# gyroscope.net
KiCad netlist of a schematic drawn in Altium Designer
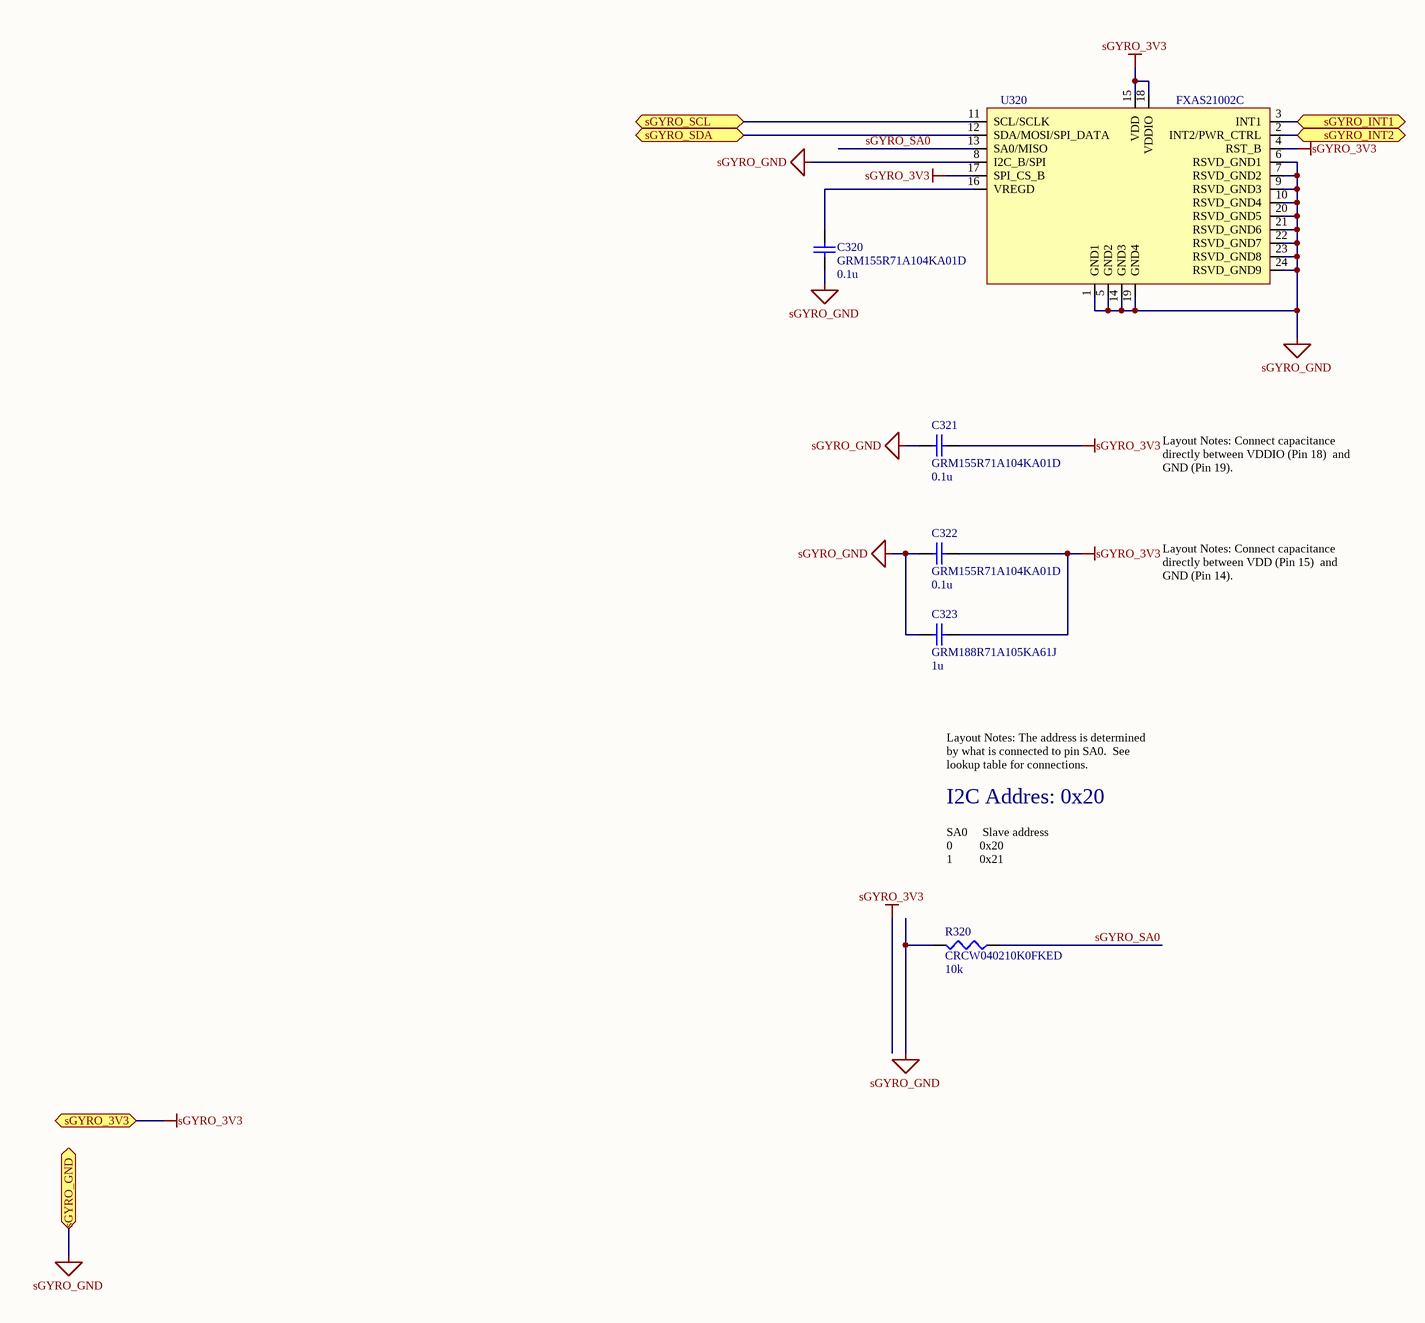
[diagram p0: _gyroscope.SchDoc]

(export (version "E")
  (design (tool "Eeschema 10.0.6"))
  (components
    (comp (ref "C320")
      (value "GRM155R71A104KA01D")
      (footprint "0402")
      (description "-55-125C, 1005, 10V, X7R, ±10%")
      (fields (field (name "ALTIUM_VALUE") "0.1u"))
      (libsource (lib "standard_capacitors") (part "GRM155R71AxxxKdddd"))
    )
    (comp (ref "C321")
      (value "GRM155R71A104KA01D")
      (footprint "0402")
      (description "-55-125C, 1005, 10V, X7R, ±10%")
      (fields (field (name "ALTIUM_VALUE") "0.1u"))
      (libsource (lib "standard_capacitors") (part "GRM155R71AxxxKdddd"))
    )
    (comp (ref "C322")
      (value "GRM155R71A104KA01D")
      (footprint "0402")
      (description "-55-125C, 1005, 10V, X7R, ±10%")
      (fields (field (name "ALTIUM_VALUE") "0.1u"))
      (libsource (lib "standard_capacitors") (part "GRM155R71AxxxKdddd"))
    )
    (comp (ref "C323")
      (value "GRM188R71A105KA61J")
      (footprint "0603")
      (description "-55-125C, 1608, 10V, X7R, ±10%")
      (fields (field (name "ALTIUM_VALUE") "1u"))
      (libsource (lib "standard_capacitors") (part "GRM188R71AxxxKdddd"))
    )
    (comp (ref "R320")
      (value "CRCW040210K0FKED")
      (footprint "0402")
      (description "0.125W, -55-155C, 1005, 50V, ±1%")
      (fields (field (name "ALTIUM_VALUE") "10k"))
      (libsource (lib "standard_resistors") (part "CRCW0402xxxxFKED"))
    )
    (comp (ref "U320")
      (value "FXAS21002C")
      (footprint "SMD QFN 24_4X4MM 7/5")
      (description "3-Axis Digital Angular Rate  Gyroscope")
      (libsource (lib "nxp") (part "FXAS21002C"))
    )
  )
  (nets
    (net (code "1") (name "/sGYRO_INT1") (class "Default")
      (node (ref "U320") (pin "3") (pinfunction "INT1_3") (pintype "passive"))
    )
    (net (code "2") (name "/sGYRO_INT2") (class "Default")
      (node (ref "U320") (pin "2") (pinfunction "INT2/PWR_CTRL_2") (pintype "passive"))
    )
    (net (code "3") (name "/sGYRO_SA0") (class "Default")
      (node (ref "R320") (pin "1") (pinfunction "1_1") (pintype "passive"))
      (node (ref "U320") (pin "13") (pinfunction "SA0/MISO_13") (pintype "passive"))
    )
    (net (code "4") (name "/sGYRO_SCL") (class "Default")
      (node (ref "U320") (pin "11") (pinfunction "SCL/SCLK_11") (pintype "passive"))
    )
    (net (code "5") (name "/sGYRO_SDA") (class "Default")
      (node (ref "U320") (pin "12") (pinfunction "SDA/MOSI/SPI_DATA_12") (pintype "passive"))
    )
    (net (code "6") (name "Net-(U320-VREGD)") (class "Default")
      (node (ref "C320") (pin "1") (pinfunction "1_1") (pintype "passive"))
      (node (ref "U320") (pin "16") (pinfunction "VREGD_16") (pintype "passive"))
    )
    (net (code "7") (name "sGYRO_3V3") (class "Default")
      (node (ref "C321") (pin "2") (pinfunction "2_2") (pintype "passive"))
      (node (ref "C322") (pin "2") (pinfunction "2_2") (pintype "passive"))
      (node (ref "C323") (pin "1") (pinfunction "1_1") (pintype "passive"))
      (node (ref "U320") (pin "15") (pinfunction "VDD_15") (pintype "passive"))
      (node (ref "U320") (pin "17") (pinfunction "SPI_CS_B_17") (pintype "passive"))
      (node (ref "U320") (pin "18") (pinfunction "VDDIO_18") (pintype "passive"))
      (node (ref "U320") (pin "4") (pinfunction "RST_B_4") (pintype "passive"))
    )
    (net (code "8") (name "sGYRO_GND") (class "Default")
      (node (ref "C320") (pin "2") (pinfunction "2_2") (pintype "passive"))
      (node (ref "C321") (pin "1") (pinfunction "1_1") (pintype "passive"))
      (node (ref "C322") (pin "1") (pinfunction "1_1") (pintype "passive"))
      (node (ref "C323") (pin "2") (pinfunction "2_2") (pintype "passive"))
      (node (ref "R320") (pin "2") (pinfunction "2_2") (pintype "passive"))
      (node (ref "U320") (pin "1") (pinfunction "GND1_1") (pintype "passive"))
      (node (ref "U320") (pin "10") (pinfunction "RSVD_GND4_10") (pintype "passive"))
      (node (ref "U320") (pin "14") (pinfunction "GND3_14") (pintype "passive"))
      (node (ref "U320") (pin "19") (pinfunction "GND4_19") (pintype "passive"))
      (node (ref "U320") (pin "20") (pinfunction "RSVD_GND5_20") (pintype "passive"))
      (node (ref "U320") (pin "21") (pinfunction "RSVD_GND6_21") (pintype "passive"))
      (node (ref "U320") (pin "22") (pinfunction "RSVD_GND7_22") (pintype "passive"))
      (node (ref "U320") (pin "23") (pinfunction "RSVD_GND8_23") (pintype "passive"))
      (node (ref "U320") (pin "24") (pinfunction "RSVD_GND9_24") (pintype "passive"))
      (node (ref "U320") (pin "5") (pinfunction "GND2_5") (pintype "passive"))
      (node (ref "U320") (pin "6") (pinfunction "RSVD_GND1_6") (pintype "passive"))
      (node (ref "U320") (pin "7") (pinfunction "RSVD_GND2_7") (pintype "passive"))
      (node (ref "U320") (pin "8") (pinfunction "I2C_B/SPI_8") (pintype "passive"))
      (node (ref "U320") (pin "9") (pinfunction "RSVD_GND3_9") (pintype "passive"))
    )
  )
)
